# untitled.net
KiCad netlist of a schematic drawn in EAGLE
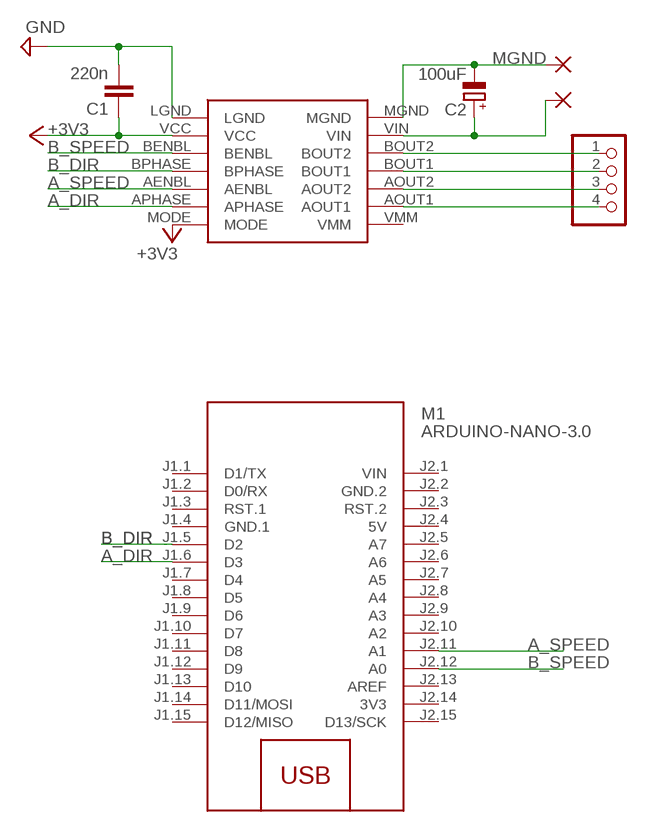
[diagram p0: schematic, sheet 1]

(export (version "E")
  (design (tool "Eeschema 10.0.6"))
  (components
    (comp (ref "C1")
      (value "220n")
      (footprint "eagle-import:C025-025X050")
      (libsource (lib "eagle-import") (part "C-EU025-025X050"))
    )
    (comp (ref "C2")
      (value "100uF")
      (footprint "eagle-import:E3,5-8")
      (libsource (lib "eagle-import") (part "CPOL-EUE3.5-8"))
    )
    (comp (ref "GND")
      (value "WIREPADSMD5-1,8")
      (footprint "eagle-import:5-1,8")
      (libsource (lib "eagle-import") (part "WIREPADSMD5-1,8"))
    )
    (comp (ref "JP1")
      (value "PINHD-1X4")
      (footprint "eagle-import:1X04")
      (libsource (lib "eagle-import") (part "PINHD-1X4"))
    )
    (comp (ref "M1")
      (value "ARDUINO-NANO-3.0")
      (footprint "eagle-import:ARDUINO-NANO-3.0")
      (libsource (lib "eagle-import") (part "ARDUINO-NANO-3.0"))
    )
    (comp (ref "U$1")
      (value "POLOLU_MOTOR_DRV8835THROUGHHOLE")
      (footprint "eagle-import:POLOLU_MOTOR_DRV_DRV8835")
      (libsource (lib "eagle-import") (part "POLOLU_MOTOR_DRV8835THROUGHHOLE"))
    )
    (comp (ref "VIN_BAT")
      (value "WIREPADSMD5-1,8")
      (footprint "eagle-import:5-1,8")
      (libsource (lib "eagle-import") (part "WIREPADSMD5-1,8"))
    )
  )
  (nets
    (net (code "1") (name "+3V3") (class "Default")
      (node (ref "C1") (pin "1") (pinfunction "1_1") (pintype "passive"))
      (node (ref "U$1") (pin "MODE") (pinfunction "MODE_MODE") (pintype "bidirectional"))
      (node (ref "U$1") (pin "VCC") (pinfunction "VCC_VCC") (pintype "bidirectional"))
    )
    (net (code "2") (name "/3V3") (class "Default")
      (node (ref "M1") (pin "J2.14") (pinfunction "3V3_J2.14") (pintype "power_in"))
    )
    (net (code "3") (name "/5V") (class "Default")
      (node (ref "M1") (pin "J2.4") (pinfunction "5V_J2.4") (pintype "power_in"))
    )
    (net (code "4") (name "/A_DIR") (class "Default")
      (node (ref "M1") (pin "J1.6") (pinfunction "D3_J1.6") (pintype "bidirectional"))
      (node (ref "U$1") (pin "APHASE") (pinfunction "APHASE_APHASE") (pintype "bidirectional"))
    )
    (net (code "5") (name "/A_SPEED") (class "Default")
      (node (ref "M1") (pin "J2.11") (pinfunction "A1_J2.11") (pintype "bidirectional"))
      (node (ref "U$1") (pin "AENBL") (pinfunction "AENBL_AENBL") (pintype "bidirectional"))
    )
    (net (code "6") (name "/B_DIR") (class "Default")
      (node (ref "M1") (pin "J1.5") (pinfunction "D2_J1.5") (pintype "bidirectional"))
      (node (ref "U$1") (pin "BPHASE") (pinfunction "BPHASE_BPHASE") (pintype "bidirectional"))
    )
    (net (code "7") (name "/B_SPEED") (class "Default")
      (node (ref "M1") (pin "J2.12") (pinfunction "A0_J2.12") (pintype "bidirectional"))
      (node (ref "U$1") (pin "BENBL") (pinfunction "BENBL_BENBL") (pintype "bidirectional"))
    )
    (net (code "8") (name "/GND.1") (class "Default")
      (node (ref "M1") (pin "J1.4") (pinfunction "GND.1_J1.4") (pintype "power_in"))
    )
    (net (code "9") (name "/GND.2") (class "Default")
      (node (ref "M1") (pin "J2.2") (pinfunction "GND.2_J2.2") (pintype "power_in"))
    )
    (net (code "10") (name "/MGND") (class "Default")
      (node (ref "C2") (pin "-") (pinfunction "-_-") (pintype "passive"))
      (node (ref "GND") (pin "1") (pinfunction "P_1") (pintype "passive"))
      (node (ref "U$1") (pin "MGND") (pinfunction "MGND_MGND") (pintype "bidirectional"))
    )
    (net (code "11") (name "/VIN") (class "Default")
      (node (ref "M1") (pin "J2.1") (pinfunction "VIN_J2.1") (pintype "power_in"))
    )
    (net (code "12") (name "GND") (class "Default")
      (node (ref "C1") (pin "2") (pinfunction "2_2") (pintype "passive"))
      (node (ref "U$1") (pin "LGND") (pinfunction "LGND_LGND") (pintype "bidirectional"))
    )
    (net (code "13") (name "Net-(JP1-Pad1)") (class "Default")
      (node (ref "JP1") (pin "1") (pinfunction "1_1") (pintype "passive"))
      (node (ref "U$1") (pin "BOUT2") (pinfunction "BOUT2_BOUT2") (pintype "bidirectional"))
    )
    (net (code "14") (name "Net-(JP1-Pad2)") (class "Default")
      (node (ref "JP1") (pin "2") (pinfunction "2_2") (pintype "passive"))
      (node (ref "U$1") (pin "BOUT1") (pinfunction "BOUT1_BOUT1") (pintype "bidirectional"))
    )
    (net (code "15") (name "Net-(JP1-Pad3)") (class "Default")
      (node (ref "JP1") (pin "3") (pinfunction "3_3") (pintype "passive"))
      (node (ref "U$1") (pin "AOUT2") (pinfunction "AOUT2_AOUT2") (pintype "bidirectional"))
    )
    (net (code "16") (name "Net-(JP1-Pad4)") (class "Default")
      (node (ref "JP1") (pin "4") (pinfunction "4_4") (pintype "passive"))
      (node (ref "U$1") (pin "AOUT1") (pinfunction "AOUT1_AOUT1") (pintype "bidirectional"))
    )
    (net (code "17") (name "Net-(VIN_BAT-P)") (class "Default")
      (node (ref "C2") (pin "+") (pinfunction "+_+") (pintype "passive"))
      (node (ref "U$1") (pin "VIN") (pinfunction "VIN_VIN") (pintype "bidirectional"))
      (node (ref "VIN_BAT") (pin "1") (pinfunction "P_1") (pintype "passive"))
    )
    (net (code "18") (name "unconnected-(M1-A2-PadJ2.10)") (class "Default")
      (node (ref "M1") (pin "J2.10") (pinfunction "A2_J2.10") (pintype "bidirectional"))
    )
    (net (code "19") (name "unconnected-(M1-A3-PadJ2.9)") (class "Default")
      (node (ref "M1") (pin "J2.9") (pinfunction "A3_J2.9") (pintype "bidirectional"))
    )
    (net (code "20") (name "unconnected-(M1-A4-PadJ2.8)") (class "Default")
      (node (ref "M1") (pin "J2.8") (pinfunction "A4_J2.8") (pintype "bidirectional"))
    )
    (net (code "21") (name "unconnected-(M1-A5-PadJ2.7)") (class "Default")
      (node (ref "M1") (pin "J2.7") (pinfunction "A5_J2.7") (pintype "bidirectional"))
    )
    (net (code "22") (name "unconnected-(M1-A6-PadJ2.6)") (class "Default")
      (node (ref "M1") (pin "J2.6") (pinfunction "A6_J2.6") (pintype "bidirectional"))
    )
    (net (code "23") (name "unconnected-(M1-A7-PadJ2.5)") (class "Default")
      (node (ref "M1") (pin "J2.5") (pinfunction "A7_J2.5") (pintype "bidirectional"))
    )
    (net (code "24") (name "unconnected-(M1-AREF-PadJ2.13)") (class "Default")
      (node (ref "M1") (pin "J2.13") (pinfunction "AREF_J2.13") (pintype "bidirectional"))
    )
    (net (code "25") (name "unconnected-(M1-D0{slash}RX-PadJ1.2)") (class "Default")
      (node (ref "M1") (pin "J1.2") (pinfunction "D0/RX_J1.2") (pintype "bidirectional"))
    )
    (net (code "26") (name "unconnected-(M1-D1{slash}TX-PadJ1.1)") (class "Default")
      (node (ref "M1") (pin "J1.1") (pinfunction "D1/TX_J1.1") (pintype "bidirectional"))
    )
    (net (code "27") (name "unconnected-(M1-D4-PadJ1.7)") (class "Default")
      (node (ref "M1") (pin "J1.7") (pinfunction "D4_J1.7") (pintype "bidirectional"))
    )
    (net (code "28") (name "unconnected-(M1-D5-PadJ1.8)") (class "Default")
      (node (ref "M1") (pin "J1.8") (pinfunction "D5_J1.8") (pintype "bidirectional"))
    )
    (net (code "29") (name "unconnected-(M1-D6-PadJ1.9)") (class "Default")
      (node (ref "M1") (pin "J1.9") (pinfunction "D6_J1.9") (pintype "bidirectional"))
    )
    (net (code "30") (name "unconnected-(M1-D7-PadJ1.10)") (class "Default")
      (node (ref "M1") (pin "J1.10") (pinfunction "D7_J1.10") (pintype "bidirectional"))
    )
    (net (code "31") (name "unconnected-(M1-D8-PadJ1.11)") (class "Default")
      (node (ref "M1") (pin "J1.11") (pinfunction "D8_J1.11") (pintype "bidirectional"))
    )
    (net (code "32") (name "unconnected-(M1-D9-PadJ1.12)") (class "Default")
      (node (ref "M1") (pin "J1.12") (pinfunction "D9_J1.12") (pintype "bidirectional"))
    )
    (net (code "33") (name "unconnected-(M1-D10-PadJ1.13)") (class "Default")
      (node (ref "M1") (pin "J1.13") (pinfunction "D10_J1.13") (pintype "bidirectional"))
    )
    (net (code "34") (name "unconnected-(M1-D11{slash}MOSI-PadJ1.14)") (class "Default")
      (node (ref "M1") (pin "J1.14") (pinfunction "D11/MOSI_J1.14") (pintype "bidirectional"))
    )
    (net (code "35") (name "unconnected-(M1-D12{slash}MISO-PadJ1.15)") (class "Default")
      (node (ref "M1") (pin "J1.15") (pinfunction "D12/MISO_J1.15") (pintype "bidirectional"))
    )
    (net (code "36") (name "unconnected-(M1-D13{slash}SCK-PadJ2.15)") (class "Default")
      (node (ref "M1") (pin "J2.15") (pinfunction "D13/SCK_J2.15") (pintype "bidirectional"))
    )
    (net (code "37") (name "unconnected-(M1-RST.1-PadJ1.3)") (class "Default")
      (node (ref "M1") (pin "J1.3") (pinfunction "RST.1_J1.3") (pintype "bidirectional"))
    )
    (net (code "38") (name "unconnected-(M1-RST.2-PadJ2.3)") (class "Default")
      (node (ref "M1") (pin "J2.3") (pinfunction "RST.2_J2.3") (pintype "bidirectional"))
    )
    (net (code "39") (name "unconnected-(U$1-PadVMM)") (class "Default")
      (node (ref "U$1") (pin "VMM") (pinfunction "VMM_VMM") (pintype "bidirectional"))
    )
  )
)
